# Amstrad-CPC-8255-PIO-2-0.net
KiCad netlist of a schematic drawn in EAGLE
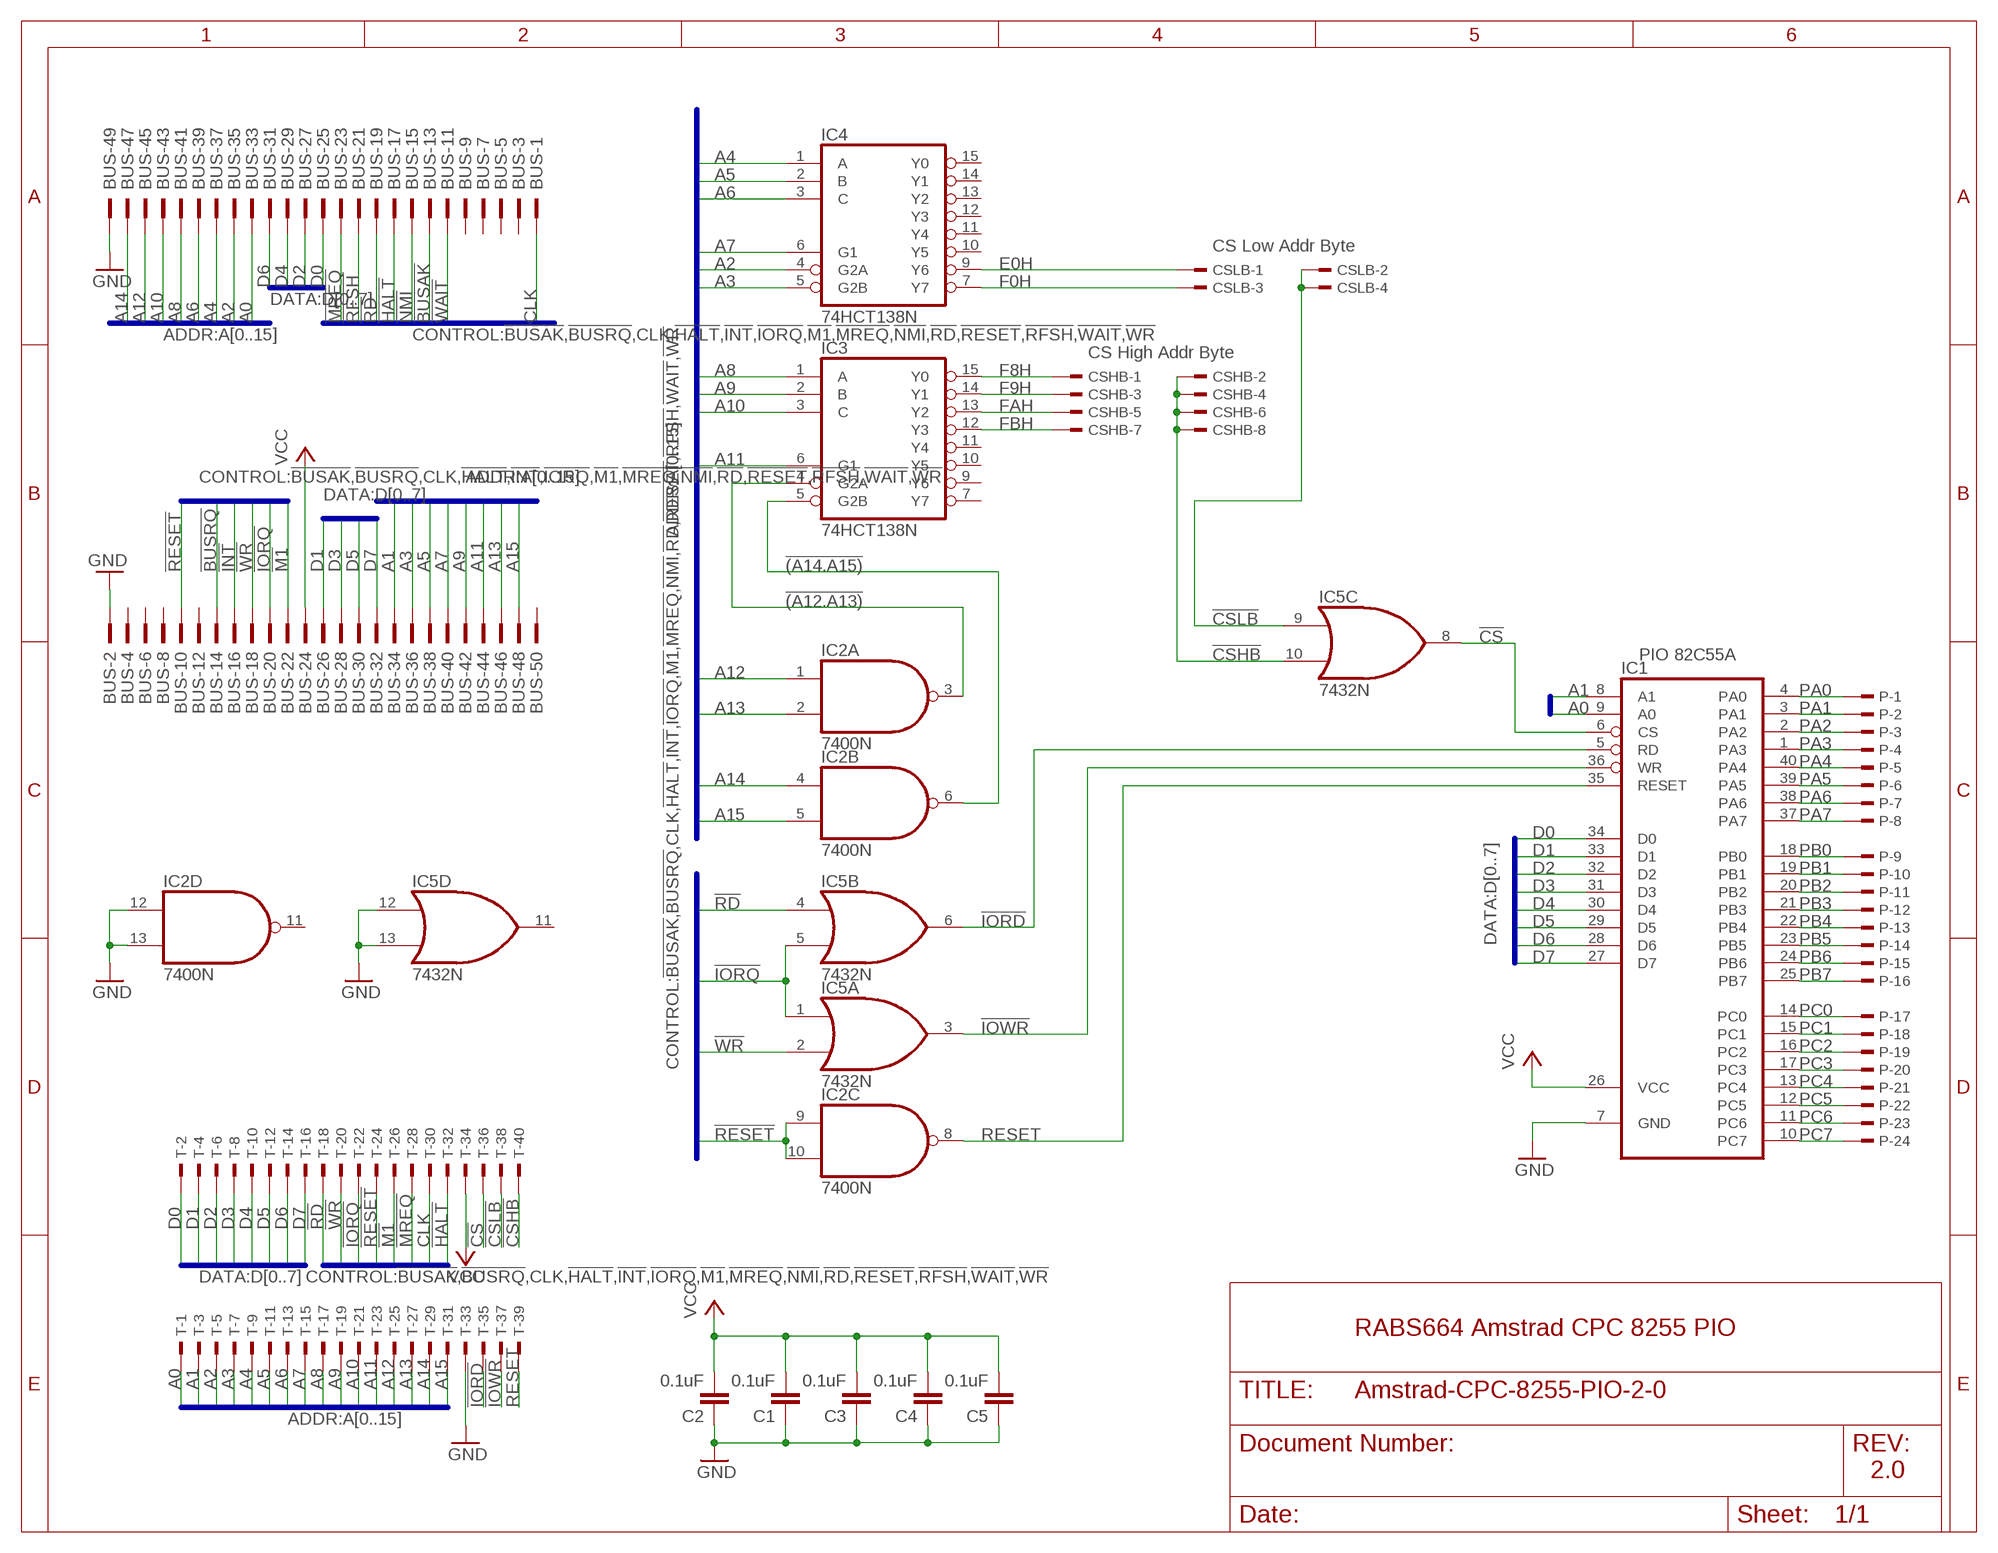
[diagram p0: schematic, sheet 1]

(export (version "E")
  (design (tool "Eeschema 10.0.6"))
  (components
    (comp (ref "BUS")
      (value "2550-")
      (footprint "eagle-import:PAK100_2500-50")
      (fields (field (name "SPICEPREFIX") "X"))
      (libsource (lib "eagle-import") (part "2550-"))
    )
    (comp (ref "C1")
      (value "0.1uF")
      (footprint "eagle-import:C050-025X075")
      (libsource (lib "eagle-import") (part "C-EU050-025X075"))
    )
    (comp (ref "C2")
      (value "0.1uF")
      (footprint "eagle-import:C050-025X075")
      (libsource (lib "eagle-import") (part "C-EU050-025X075"))
    )
    (comp (ref "C3")
      (value "0.1uF")
      (footprint "eagle-import:C050-025X075")
      (libsource (lib "eagle-import") (part "C-EU050-025X075"))
    )
    (comp (ref "C4")
      (value "0.1uF")
      (footprint "eagle-import:C050-025X075")
      (libsource (lib "eagle-import") (part "C-EU050-025X075"))
    )
    (comp (ref "C5")
      (value "0.1uF")
      (footprint "eagle-import:C050-025X075")
      (libsource (lib "eagle-import") (part "C-EU050-025X075"))
    )
    (comp (ref "CSHB")
      (value "TSW-104-07-G-D")
      (footprint "eagle-import:TSW-104-XX-G-D")
      (fields (field (name "MF") "Samtec Inc."))
      (libsource (lib "eagle-import") (part "TSW-104--G-D07"))
    )
    (comp (ref "CSLB")
      (value "TSW-102-07-G-D")
      (footprint "eagle-import:TSW-102-XX-G-D")
      (fields (field (name "MF") "Samtec Inc."))
      (libsource (lib "eagle-import") (part "TSW-102--G-D07"))
    )
    (comp (ref "IC1")
      (value "82C55A")
      (footprint "eagle-import:DIL40")
      (fields (field (name "MF") "INTERSIL") (field (name "MPN") "IP82C55AZ"))
      (libsource (lib "eagle-import") (part "82C55A"))
    )
    (comp (ref "IC2")
      (value "7400N")
      (footprint "eagle-import:DIL14")
      (libsource (lib "eagle-import") (part "7400N"))
    )
    (comp (ref "IC3")
      (value "74HCT138N")
      (footprint "eagle-import:DIL16")
      (libsource (lib "eagle-import") (part "74138NHCT"))
    )
    (comp (ref "IC4")
      (value "74HCT138N")
      (footprint "eagle-import:DIL16")
      (libsource (lib "eagle-import") (part "74138NHCT"))
    )
    (comp (ref "IC5")
      (value "7432N")
      (footprint "eagle-import:DIL14")
      (libsource (lib "eagle-import") (part "7432N"))
    )
    (comp (ref "P")
      (value "TSW-124-07-G-S")
      (footprint "eagle-import:TSW-124-XX-G-S")
      (fields (field (name "MF") "Samtec Inc."))
      (libsource (lib "eagle-import") (part "TSW-124--G-S07"))
    )
    (comp (ref "T")
      (value "TSW-120-07-G-D")
      (footprint "eagle-import:TSW-120-XX-G-D")
      (fields (field (name "MF") "Samtec Inc."))
      (libsource (lib "eagle-import") (part "TSW-120--G-D07"))
    )
  )
  (nets
    (net (code "29") (name "A0") (class "Default")
      (node (ref "BUS") (pin "33") (pinfunction "KL_33") (pintype "passive"))
      (node (ref "IC1") (pin "9") (pinfunction "A0_9") (pintype "input"))
      (node (ref "T") (pin "1") (pinfunction "1_1") (pintype "passive"))
    )
    (net (code "30") (name "A1") (class "Default")
      (node (ref "BUS") (pin "34") (pinfunction "KL_34") (pintype "passive"))
      (node (ref "IC1") (pin "8") (pinfunction "A1_8") (pintype "input"))
      (node (ref "T") (pin "3") (pinfunction "1_3") (pintype "passive"))
    )
    (net (code "31") (name "A2") (class "Default")
      (node (ref "BUS") (pin "35") (pinfunction "KL_35") (pintype "passive"))
      (node (ref "IC4") (pin "4") (pinfunction "G2A_4") (pintype "input"))
      (node (ref "T") (pin "5") (pinfunction "1_5") (pintype "passive"))
    )
    (net (code "32") (name "A3") (class "Default")
      (node (ref "BUS") (pin "36") (pinfunction "KL_36") (pintype "passive"))
      (node (ref "IC4") (pin "5") (pinfunction "G2B_5") (pintype "input"))
      (node (ref "T") (pin "7") (pinfunction "1_7") (pintype "passive"))
    )
    (net (code "33") (name "A4") (class "Default")
      (node (ref "BUS") (pin "37") (pinfunction "KL_37") (pintype "passive"))
      (node (ref "IC4") (pin "1") (pinfunction "A_1") (pintype "input"))
      (node (ref "T") (pin "9") (pinfunction "1_9") (pintype "passive"))
    )
    (net (code "34") (name "A5") (class "Default")
      (node (ref "BUS") (pin "38") (pinfunction "KL_38") (pintype "passive"))
      (node (ref "IC4") (pin "2") (pinfunction "B_2") (pintype "input"))
      (node (ref "T") (pin "11") (pinfunction "1_11") (pintype "passive"))
    )
    (net (code "35") (name "A6") (class "Default")
      (node (ref "BUS") (pin "39") (pinfunction "KL_39") (pintype "passive"))
      (node (ref "IC4") (pin "3") (pinfunction "C_3") (pintype "input"))
      (node (ref "T") (pin "13") (pinfunction "1_13") (pintype "passive"))
    )
    (net (code "36") (name "A7") (class "Default")
      (node (ref "BUS") (pin "40") (pinfunction "KL_40") (pintype "passive"))
      (node (ref "IC4") (pin "6") (pinfunction "G1_6") (pintype "input"))
      (node (ref "T") (pin "15") (pinfunction "1_15") (pintype "passive"))
    )
    (net (code "37") (name "A8") (class "Default")
      (node (ref "BUS") (pin "41") (pinfunction "KL_41") (pintype "passive"))
      (node (ref "IC3") (pin "1") (pinfunction "A_1") (pintype "input"))
      (node (ref "T") (pin "17") (pinfunction "1_17") (pintype "passive"))
    )
    (net (code "38") (name "A9") (class "Default")
      (node (ref "BUS") (pin "42") (pinfunction "KL_42") (pintype "passive"))
      (node (ref "IC3") (pin "2") (pinfunction "B_2") (pintype "input"))
      (node (ref "T") (pin "19") (pinfunction "1_19") (pintype "passive"))
    )
    (net (code "39") (name "A10") (class "Default")
      (node (ref "BUS") (pin "43") (pinfunction "KL_43") (pintype "passive"))
      (node (ref "IC3") (pin "3") (pinfunction "C_3") (pintype "input"))
      (node (ref "T") (pin "21") (pinfunction "1_21") (pintype "passive"))
    )
    (net (code "40") (name "A11") (class "Default")
      (node (ref "BUS") (pin "44") (pinfunction "KL_44") (pintype "passive"))
      (node (ref "IC3") (pin "6") (pinfunction "G1_6") (pintype "input"))
      (node (ref "T") (pin "23") (pinfunction "1_23") (pintype "passive"))
    )
    (net (code "41") (name "A12") (class "Default")
      (node (ref "BUS") (pin "45") (pinfunction "KL_45") (pintype "passive"))
      (node (ref "IC2") (pin "1") (pinfunction "I0_1") (pintype "input"))
      (node (ref "T") (pin "25") (pinfunction "1_25") (pintype "passive"))
    )
    (net (code "42") (name "A13") (class "Default")
      (node (ref "BUS") (pin "46") (pinfunction "KL_46") (pintype "passive"))
      (node (ref "IC2") (pin "2") (pinfunction "I1_2") (pintype "input"))
      (node (ref "T") (pin "27") (pinfunction "1_27") (pintype "passive"))
    )
    (net (code "43") (name "A14") (class "Default")
      (node (ref "BUS") (pin "47") (pinfunction "KL_47") (pintype "passive"))
      (node (ref "IC2") (pin "4") (pinfunction "I0_4") (pintype "input"))
      (node (ref "T") (pin "29") (pinfunction "1_29") (pintype "passive"))
    )
    (net (code "44") (name "A15") (class "Default")
      (node (ref "BUS") (pin "48") (pinfunction "KL_48") (pintype "passive"))
      (node (ref "IC2") (pin "5") (pinfunction "I1_5") (pintype "input"))
      (node (ref "T") (pin "31") (pinfunction "1_31") (pintype "passive"))
    )
    (net (code "45") (name "CLK") (class "Default")
      (node (ref "BUS") (pin "1") (pinfunction "KL_1") (pintype "passive"))
      (node (ref "T") (pin "30") (pinfunction "1_30") (pintype "passive"))
    )
    (net (code "46") (name "D0") (class "Default")
      (node (ref "BUS") (pin "25") (pinfunction "KL_25") (pintype "passive"))
      (node (ref "IC1") (pin "34") (pinfunction "D0_34") (pintype "bidirectional"))
      (node (ref "T") (pin "2") (pinfunction "1_2") (pintype "passive"))
    )
    (net (code "47") (name "D1") (class "Default")
      (node (ref "BUS") (pin "26") (pinfunction "KL_26") (pintype "passive"))
      (node (ref "IC1") (pin "33") (pinfunction "D1_33") (pintype "bidirectional"))
      (node (ref "T") (pin "4") (pinfunction "1_4") (pintype "passive"))
    )
    (net (code "48") (name "D2") (class "Default")
      (node (ref "BUS") (pin "27") (pinfunction "KL_27") (pintype "passive"))
      (node (ref "IC1") (pin "32") (pinfunction "D2_32") (pintype "bidirectional"))
      (node (ref "T") (pin "6") (pinfunction "1_6") (pintype "passive"))
    )
    (net (code "49") (name "D3") (class "Default")
      (node (ref "BUS") (pin "28") (pinfunction "KL_28") (pintype "passive"))
      (node (ref "IC1") (pin "31") (pinfunction "D3_31") (pintype "bidirectional"))
      (node (ref "T") (pin "8") (pinfunction "1_8") (pintype "passive"))
    )
    (net (code "50") (name "D4") (class "Default")
      (node (ref "BUS") (pin "29") (pinfunction "KL_29") (pintype "passive"))
      (node (ref "IC1") (pin "30") (pinfunction "D4_30") (pintype "bidirectional"))
      (node (ref "T") (pin "10") (pinfunction "1_10") (pintype "passive"))
    )
    (net (code "51") (name "D5") (class "Default")
      (node (ref "BUS") (pin "30") (pinfunction "KL_30") (pintype "passive"))
      (node (ref "IC1") (pin "29") (pinfunction "D5_29") (pintype "bidirectional"))
      (node (ref "T") (pin "12") (pinfunction "1_12") (pintype "passive"))
    )
    (net (code "52") (name "D6") (class "Default")
      (node (ref "BUS") (pin "31") (pinfunction "KL_31") (pintype "passive"))
      (node (ref "IC1") (pin "28") (pinfunction "D6_28") (pintype "bidirectional"))
      (node (ref "T") (pin "14") (pinfunction "1_14") (pintype "passive"))
    )
    (net (code "53") (name "D7") (class "Default")
      (node (ref "BUS") (pin "32") (pinfunction "KL_32") (pintype "passive"))
      (node (ref "IC1") (pin "27") (pinfunction "D7_27") (pintype "bidirectional"))
      (node (ref "T") (pin "16") (pinfunction "1_16") (pintype "passive"))
    )
    (net (code "54") (name "E0H") (class "Default")
      (node (ref "CSLB") (pin "1") (pinfunction "1_1") (pintype "passive"))
      (node (ref "IC4") (pin "9") (pinfunction "Y6_9") (pintype "output"))
    )
    (net (code "55") (name "F0H") (class "Default")
      (node (ref "CSLB") (pin "3") (pinfunction "1_3") (pintype "passive"))
      (node (ref "IC4") (pin "7") (pinfunction "Y7_7") (pintype "output"))
    )
    (net (code "56") (name "F8H") (class "Default")
      (node (ref "CSHB") (pin "1") (pinfunction "1_1") (pintype "passive"))
      (node (ref "IC3") (pin "15") (pinfunction "Y0_15") (pintype "output"))
    )
    (net (code "57") (name "F9H") (class "Default")
      (node (ref "CSHB") (pin "3") (pinfunction "1_3") (pintype "passive"))
      (node (ref "IC3") (pin "14") (pinfunction "Y1_14") (pintype "output"))
    )
    (net (code "58") (name "FAH") (class "Default")
      (node (ref "CSHB") (pin "5") (pinfunction "1_5") (pintype "passive"))
      (node (ref "IC3") (pin "13") (pinfunction "Y2_13") (pintype "output"))
    )
    (net (code "59") (name "FBH") (class "Default")
      (node (ref "CSHB") (pin "7") (pinfunction "1_7") (pintype "passive"))
      (node (ref "IC3") (pin "12") (pinfunction "Y3_12") (pintype "output"))
    )
    (net (code "60") (name "GND") (class "Default")
      (node (ref "BUS") (pin "2") (pinfunction "KL_2") (pintype "passive"))
      (node (ref "BUS") (pin "49") (pinfunction "KL_49") (pintype "passive"))
      (node (ref "C1") (pin "1") (pinfunction "1_1") (pintype "passive"))
      (node (ref "C2") (pin "1") (pinfunction "1_1") (pintype "passive"))
      (node (ref "C3") (pin "1") (pinfunction "1_1") (pintype "passive"))
      (node (ref "C4") (pin "1") (pinfunction "1_1") (pintype "passive"))
      (node (ref "C5") (pin "1") (pinfunction "1_1") (pintype "passive"))
      (node (ref "IC1") (pin "7") (pinfunction "GND_7") (pintype "power_in"))
      (node (ref "IC2") (pin "12") (pinfunction "I0_12") (pintype "input"))
      (node (ref "IC2") (pin "13") (pinfunction "I1_13") (pintype "input"))
      (node (ref "IC5") (pin "12") (pinfunction "I0_12") (pintype "input"))
      (node (ref "IC5") (pin "13") (pinfunction "I1_13") (pintype "input"))
      (node (ref "T") (pin "33") (pinfunction "1_33") (pintype "passive"))
    )
    (net (code "61") (name "PA0") (class "Default")
      (node (ref "IC1") (pin "4") (pinfunction "PA0_4") (pintype "bidirectional"))
      (node (ref "P") (pin "1") (pinfunction "1_1") (pintype "passive"))
    )
    (net (code "62") (name "PA1") (class "Default")
      (node (ref "IC1") (pin "3") (pinfunction "PA1_3") (pintype "bidirectional"))
      (node (ref "P") (pin "2") (pinfunction "1_2") (pintype "passive"))
    )
    (net (code "63") (name "PA2") (class "Default")
      (node (ref "IC1") (pin "2") (pinfunction "PA2_2") (pintype "bidirectional"))
      (node (ref "P") (pin "3") (pinfunction "1_3") (pintype "passive"))
    )
    (net (code "64") (name "PA3") (class "Default")
      (node (ref "IC1") (pin "1") (pinfunction "PA3_1") (pintype "bidirectional"))
      (node (ref "P") (pin "4") (pinfunction "1_4") (pintype "passive"))
    )
    (net (code "65") (name "PA4") (class "Default")
      (node (ref "IC1") (pin "40") (pinfunction "PA4_40") (pintype "bidirectional"))
      (node (ref "P") (pin "5") (pinfunction "1_5") (pintype "passive"))
    )
    (net (code "66") (name "PA5") (class "Default")
      (node (ref "IC1") (pin "39") (pinfunction "PA5_39") (pintype "bidirectional"))
      (node (ref "P") (pin "6") (pinfunction "1_6") (pintype "passive"))
    )
    (net (code "67") (name "PA6") (class "Default")
      (node (ref "IC1") (pin "38") (pinfunction "PA6_38") (pintype "bidirectional"))
      (node (ref "P") (pin "7") (pinfunction "1_7") (pintype "passive"))
    )
    (net (code "68") (name "PA7") (class "Default")
      (node (ref "IC1") (pin "37") (pinfunction "PA7_37") (pintype "bidirectional"))
      (node (ref "P") (pin "8") (pinfunction "1_8") (pintype "passive"))
    )
    (net (code "69") (name "PB0") (class "Default")
      (node (ref "IC1") (pin "18") (pinfunction "PB0_18") (pintype "bidirectional"))
      (node (ref "P") (pin "9") (pinfunction "1_9") (pintype "passive"))
    )
    (net (code "70") (name "PB1") (class "Default")
      (node (ref "IC1") (pin "19") (pinfunction "PB1_19") (pintype "bidirectional"))
      (node (ref "P") (pin "10") (pinfunction "1_10") (pintype "passive"))
    )
    (net (code "71") (name "PB2") (class "Default")
      (node (ref "IC1") (pin "20") (pinfunction "PB2_20") (pintype "bidirectional"))
      (node (ref "P") (pin "11") (pinfunction "1_11") (pintype "passive"))
    )
    (net (code "72") (name "PB3") (class "Default")
      (node (ref "IC1") (pin "21") (pinfunction "PB3_21") (pintype "bidirectional"))
      (node (ref "P") (pin "12") (pinfunction "1_12") (pintype "passive"))
    )
    (net (code "73") (name "PB4") (class "Default")
      (node (ref "IC1") (pin "22") (pinfunction "PB4_22") (pintype "bidirectional"))
      (node (ref "P") (pin "13") (pinfunction "1_13") (pintype "passive"))
    )
    (net (code "74") (name "PB5") (class "Default")
      (node (ref "IC1") (pin "23") (pinfunction "PB5_23") (pintype "bidirectional"))
      (node (ref "P") (pin "14") (pinfunction "1_14") (pintype "passive"))
    )
    (net (code "75") (name "PB6") (class "Default")
      (node (ref "IC1") (pin "24") (pinfunction "PB6_24") (pintype "bidirectional"))
      (node (ref "P") (pin "15") (pinfunction "1_15") (pintype "passive"))
    )
    (net (code "76") (name "PB7") (class "Default")
      (node (ref "IC1") (pin "25") (pinfunction "PB7_25") (pintype "bidirectional"))
      (node (ref "P") (pin "16") (pinfunction "1_16") (pintype "passive"))
    )
    (net (code "77") (name "PC0") (class "Default")
      (node (ref "IC1") (pin "14") (pinfunction "PC0_14") (pintype "bidirectional"))
      (node (ref "P") (pin "17") (pinfunction "1_17") (pintype "passive"))
    )
    (net (code "78") (name "PC1") (class "Default")
      (node (ref "IC1") (pin "15") (pinfunction "PC1_15") (pintype "bidirectional"))
      (node (ref "P") (pin "18") (pinfunction "1_18") (pintype "passive"))
    )
    (net (code "79") (name "PC2") (class "Default")
      (node (ref "IC1") (pin "16") (pinfunction "PC2_16") (pintype "bidirectional"))
      (node (ref "P") (pin "19") (pinfunction "1_19") (pintype "passive"))
    )
    (net (code "80") (name "PC3") (class "Default")
      (node (ref "IC1") (pin "17") (pinfunction "PC3_17") (pintype "bidirectional"))
      (node (ref "P") (pin "20") (pinfunction "1_20") (pintype "passive"))
    )
    (net (code "81") (name "PC4") (class "Default")
      (node (ref "IC1") (pin "13") (pinfunction "PC4_13") (pintype "bidirectional"))
      (node (ref "P") (pin "21") (pinfunction "1_21") (pintype "passive"))
    )
    (net (code "82") (name "PC5") (class "Default")
      (node (ref "IC1") (pin "12") (pinfunction "PC5_12") (pintype "bidirectional"))
      (node (ref "P") (pin "22") (pinfunction "1_22") (pintype "passive"))
    )
    (net (code "83") (name "PC6") (class "Default")
      (node (ref "IC1") (pin "11") (pinfunction "PC6_11") (pintype "bidirectional"))
      (node (ref "P") (pin "23") (pinfunction "1_23") (pintype "passive"))
    )
    (net (code "84") (name "PC7") (class "Default")
      (node (ref "IC1") (pin "10") (pinfunction "PC7_10") (pintype "bidirectional"))
      (node (ref "P") (pin "24") (pinfunction "1_24") (pintype "passive"))
    )
    (net (code "85") (name "RESET") (class "Default")
      (node (ref "IC1") (pin "35") (pinfunction "RESET_35") (pintype "input"))
      (node (ref "IC2") (pin "8") (pinfunction "O_8") (pintype "output"))
      (node (ref "T") (pin "39") (pinfunction "1_39") (pintype "passive"))
    )
    (net (code "86") (name "VCC") (class "Default")
      (node (ref "BUS") (pin "24") (pinfunction "KL_24") (pintype "passive"))
      (node (ref "C1") (pin "2") (pinfunction "2_2") (pintype "passive"))
      (node (ref "C2") (pin "2") (pinfunction "2_2") (pintype "passive"))
      (node (ref "C3") (pin "2") (pinfunction "2_2") (pintype "passive"))
      (node (ref "C4") (pin "2") (pinfunction "2_2") (pintype "passive"))
      (node (ref "C5") (pin "2") (pinfunction "2_2") (pintype "passive"))
      (node (ref "IC1") (pin "26") (pinfunction "VCC_26") (pintype "power_in"))
      (node (ref "T") (pin "34") (pinfunction "1_34") (pintype "passive"))
    )
    (net (code "87") (name "unconnected-(BUSAH-KL-Pad4)") (class "Default")
      (node (ref "BUS") (pin "4") (pinfunction "KL_4") (pintype "passive"))
    )
    (net (code "88") (name "unconnected-(BUSAS-KL-Pad5)") (class "Default")
      (node (ref "BUS") (pin "5") (pinfunction "KL_5") (pintype "passive"))
    )
    (net (code "89") (name "unconnected-(BUSAT-KL-Pad50)") (class "Default")
      (node (ref "BUS") (pin "50") (pinfunction "KL_50") (pintype "passive"))
    )
    (net (code "90") (name "unconnected-(BUSAU-KL-Pad6)") (class "Default")
      (node (ref "BUS") (pin "6") (pinfunction "KL_6") (pintype "passive"))
    )
    (net (code "91") (name "unconnected-(BUSAV-KL-Pad7)") (class "Default")
      (node (ref "BUS") (pin "7") (pinfunction "KL_7") (pintype "passive"))
    )
    (net (code "92") (name "unconnected-(BUSAW-KL-Pad8)") (class "Default")
      (node (ref "BUS") (pin "8") (pinfunction "KL_8") (pintype "passive"))
    )
    (net (code "93") (name "unconnected-(BUSAX-KL-Pad9)") (class "Default")
      (node (ref "BUS") (pin "9") (pinfunction "KL_9") (pintype "passive"))
    )
    (net (code "94") (name "unconnected-(BUSD-KL-Pad12)") (class "Default")
      (node (ref "BUS") (pin "12") (pinfunction "KL_12") (pintype "passive"))
    )
    (net (code "95") (name "unconnected-(BUSW-KL-Pad3)") (class "Default")
      (node (ref "BUS") (pin "3") (pinfunction "KL_3") (pintype "passive"))
    )
    (net (code "96") (name "unconnected-(IC2D-O-Pad11)") (class "Default")
      (node (ref "IC2") (pin "11") (pinfunction "O_11") (pintype "output"))
    )
    (net (code "97") (name "unconnected-(IC3A-Y4-Pad11)") (class "Default")
      (node (ref "IC3") (pin "11") (pinfunction "Y4_11") (pintype "output"))
    )
    (net (code "98") (name "unconnected-(IC3A-Y5-Pad10)") (class "Default")
      (node (ref "IC3") (pin "10") (pinfunction "Y5_10") (pintype "output"))
    )
    (net (code "99") (name "unconnected-(IC3A-Y6-Pad9)") (class "Default")
      (node (ref "IC3") (pin "9") (pinfunction "Y6_9") (pintype "output"))
    )
    (net (code "100") (name "unconnected-(IC3A-Y7-Pad7)") (class "Default")
      (node (ref "IC3") (pin "7") (pinfunction "Y7_7") (pintype "output"))
    )
    (net (code "101") (name "unconnected-(IC4A-Y0-Pad15)") (class "Default")
      (node (ref "IC4") (pin "15") (pinfunction "Y0_15") (pintype "output"))
    )
    (net (code "102") (name "unconnected-(IC4A-Y1-Pad14)") (class "Default")
      (node (ref "IC4") (pin "14") (pinfunction "Y1_14") (pintype "output"))
    )
    (net (code "103") (name "unconnected-(IC4A-Y2-Pad13)") (class "Default")
      (node (ref "IC4") (pin "13") (pinfunction "Y2_13") (pintype "output"))
    )
    (net (code "104") (name "unconnected-(IC4A-Y3-Pad12)") (class "Default")
      (node (ref "IC4") (pin "12") (pinfunction "Y3_12") (pintype "output"))
    )
    (net (code "105") (name "unconnected-(IC4A-Y4-Pad11)") (class "Default")
      (node (ref "IC4") (pin "11") (pinfunction "Y4_11") (pintype "output"))
    )
    (net (code "106") (name "unconnected-(IC4A-Y5-Pad10)") (class "Default")
      (node (ref "IC4") (pin "10") (pinfunction "Y5_10") (pintype "output"))
    )
    (net (code "107") (name "unconnected-(IC5D-O-Pad11)") (class "Default")
      (node (ref "IC5") (pin "11") (pinfunction "O_11") (pintype "output"))
    )
    (net (code "108") (name "~{(A12.A13})") (class "Default")
      (node (ref "IC2") (pin "3") (pinfunction "O_3") (pintype "output"))
      (node (ref "IC3") (pin "4") (pinfunction "G2A_4") (pintype "input"))
    )
    (net (code "109") (name "~{(A14.A15})") (class "Default")
      (node (ref "IC2") (pin "6") (pinfunction "O_6") (pintype "output"))
      (node (ref "IC3") (pin "5") (pinfunction "G2B_5") (pintype "input"))
    )
    (net (code "110") (name "~{BUSAK}") (class "Default")
      (node (ref "BUS") (pin "13") (pinfunction "KL_13") (pintype "passive"))
    )
    (net (code "111") (name "~{BUSRQ}") (class "Default")
      (node (ref "BUS") (pin "14") (pinfunction "KL_14") (pintype "passive"))
    )
    (net (code "112") (name "~{CSHB}") (class "Default")
      (node (ref "CSHB") (pin "2") (pinfunction "1_2") (pintype "passive"))
      (node (ref "CSHB") (pin "4") (pinfunction "1_4") (pintype "passive"))
      (node (ref "CSHB") (pin "6") (pinfunction "1_6") (pintype "passive"))
      (node (ref "CSHB") (pin "8") (pinfunction "1_8") (pintype "passive"))
      (node (ref "IC5") (pin "10") (pinfunction "I1_10") (pintype "input"))
      (node (ref "T") (pin "40") (pinfunction "1_40") (pintype "passive"))
    )
    (net (code "113") (name "~{CSLB}") (class "Default")
      (node (ref "CSLB") (pin "2") (pinfunction "1_2") (pintype "passive"))
      (node (ref "CSLB") (pin "4") (pinfunction "1_4") (pintype "passive"))
      (node (ref "IC5") (pin "9") (pinfunction "I0_9") (pintype "input"))
      (node (ref "T") (pin "38") (pinfunction "1_38") (pintype "passive"))
    )
    (net (code "114") (name "~{CS}") (class "Default")
      (node (ref "IC1") (pin "6") (pinfunction "CS_6") (pintype "input"))
      (node (ref "IC5") (pin "8") (pinfunction "O_8") (pintype "output"))
      (node (ref "T") (pin "36") (pinfunction "1_36") (pintype "passive"))
    )
    (net (code "115") (name "~{HALT}") (class "Default")
      (node (ref "BUS") (pin "17") (pinfunction "KL_17") (pintype "passive"))
      (node (ref "T") (pin "32") (pinfunction "1_32") (pintype "passive"))
    )
    (net (code "116") (name "~{INT}") (class "Default")
      (node (ref "BUS") (pin "16") (pinfunction "KL_16") (pintype "passive"))
    )
    (net (code "117") (name "~{IORD}") (class "Default")
      (node (ref "IC1") (pin "5") (pinfunction "RD_5") (pintype "input"))
      (node (ref "IC5") (pin "6") (pinfunction "O_6") (pintype "output"))
      (node (ref "T") (pin "35") (pinfunction "1_35") (pintype "passive"))
    )
    (net (code "118") (name "~{IORQ}") (class "Default")
      (node (ref "BUS") (pin "20") (pinfunction "KL_20") (pintype "passive"))
      (node (ref "IC5") (pin "1") (pinfunction "I0_1") (pintype "input"))
      (node (ref "IC5") (pin "5") (pinfunction "I1_5") (pintype "input"))
      (node (ref "T") (pin "22") (pinfunction "1_22") (pintype "passive"))
    )
    (net (code "119") (name "~{IOWR}") (class "Default")
      (node (ref "IC1") (pin "36") (pinfunction "WR_36") (pintype "input"))
      (node (ref "IC5") (pin "3") (pinfunction "O_3") (pintype "output"))
      (node (ref "T") (pin "37") (pinfunction "1_37") (pintype "passive"))
    )
    (net (code "120") (name "~{M1}") (class "Default")
      (node (ref "BUS") (pin "22") (pinfunction "KL_22") (pintype "passive"))
      (node (ref "T") (pin "26") (pinfunction "1_26") (pintype "passive"))
    )
    (net (code "121") (name "~{MREQ}") (class "Default")
      (node (ref "BUS") (pin "23") (pinfunction "KL_23") (pintype "passive"))
      (node (ref "T") (pin "28") (pinfunction "1_28") (pintype "passive"))
    )
    (net (code "122") (name "~{NMI}") (class "Default")
      (node (ref "BUS") (pin "15") (pinfunction "KL_15") (pintype "passive"))
    )
    (net (code "123") (name "~{RD}") (class "Default")
      (node (ref "BUS") (pin "19") (pinfunction "KL_19") (pintype "passive"))
      (node (ref "IC5") (pin "4") (pinfunction "I0_4") (pintype "input"))
      (node (ref "T") (pin "18") (pinfunction "1_18") (pintype "passive"))
    )
    (net (code "124") (name "~{RESET}") (class "Default")
      (node (ref "BUS") (pin "10") (pinfunction "KL_10") (pintype "passive"))
      (node (ref "IC2") (pin "10") (pinfunction "I1_10") (pintype "input"))
      (node (ref "IC2") (pin "9") (pinfunction "I0_9") (pintype "input"))
      (node (ref "T") (pin "24") (pinfunction "1_24") (pintype "passive"))
    )
    (net (code "125") (name "~{RFSH}") (class "Default")
      (node (ref "BUS") (pin "21") (pinfunction "KL_21") (pintype "passive"))
    )
    (net (code "126") (name "~{WAIT}") (class "Default")
      (node (ref "BUS") (pin "11") (pinfunction "KL_11") (pintype "passive"))
    )
    (net (code "127") (name "~{WR}") (class "Default")
      (node (ref "BUS") (pin "18") (pinfunction "KL_18") (pintype "passive"))
      (node (ref "IC5") (pin "2") (pinfunction "I1_2") (pintype "input"))
      (node (ref "T") (pin "20") (pinfunction "1_20") (pintype "passive"))
    )
  )
)
